# untitled.net
KiCad netlist of a schematic drawn in EAGLE
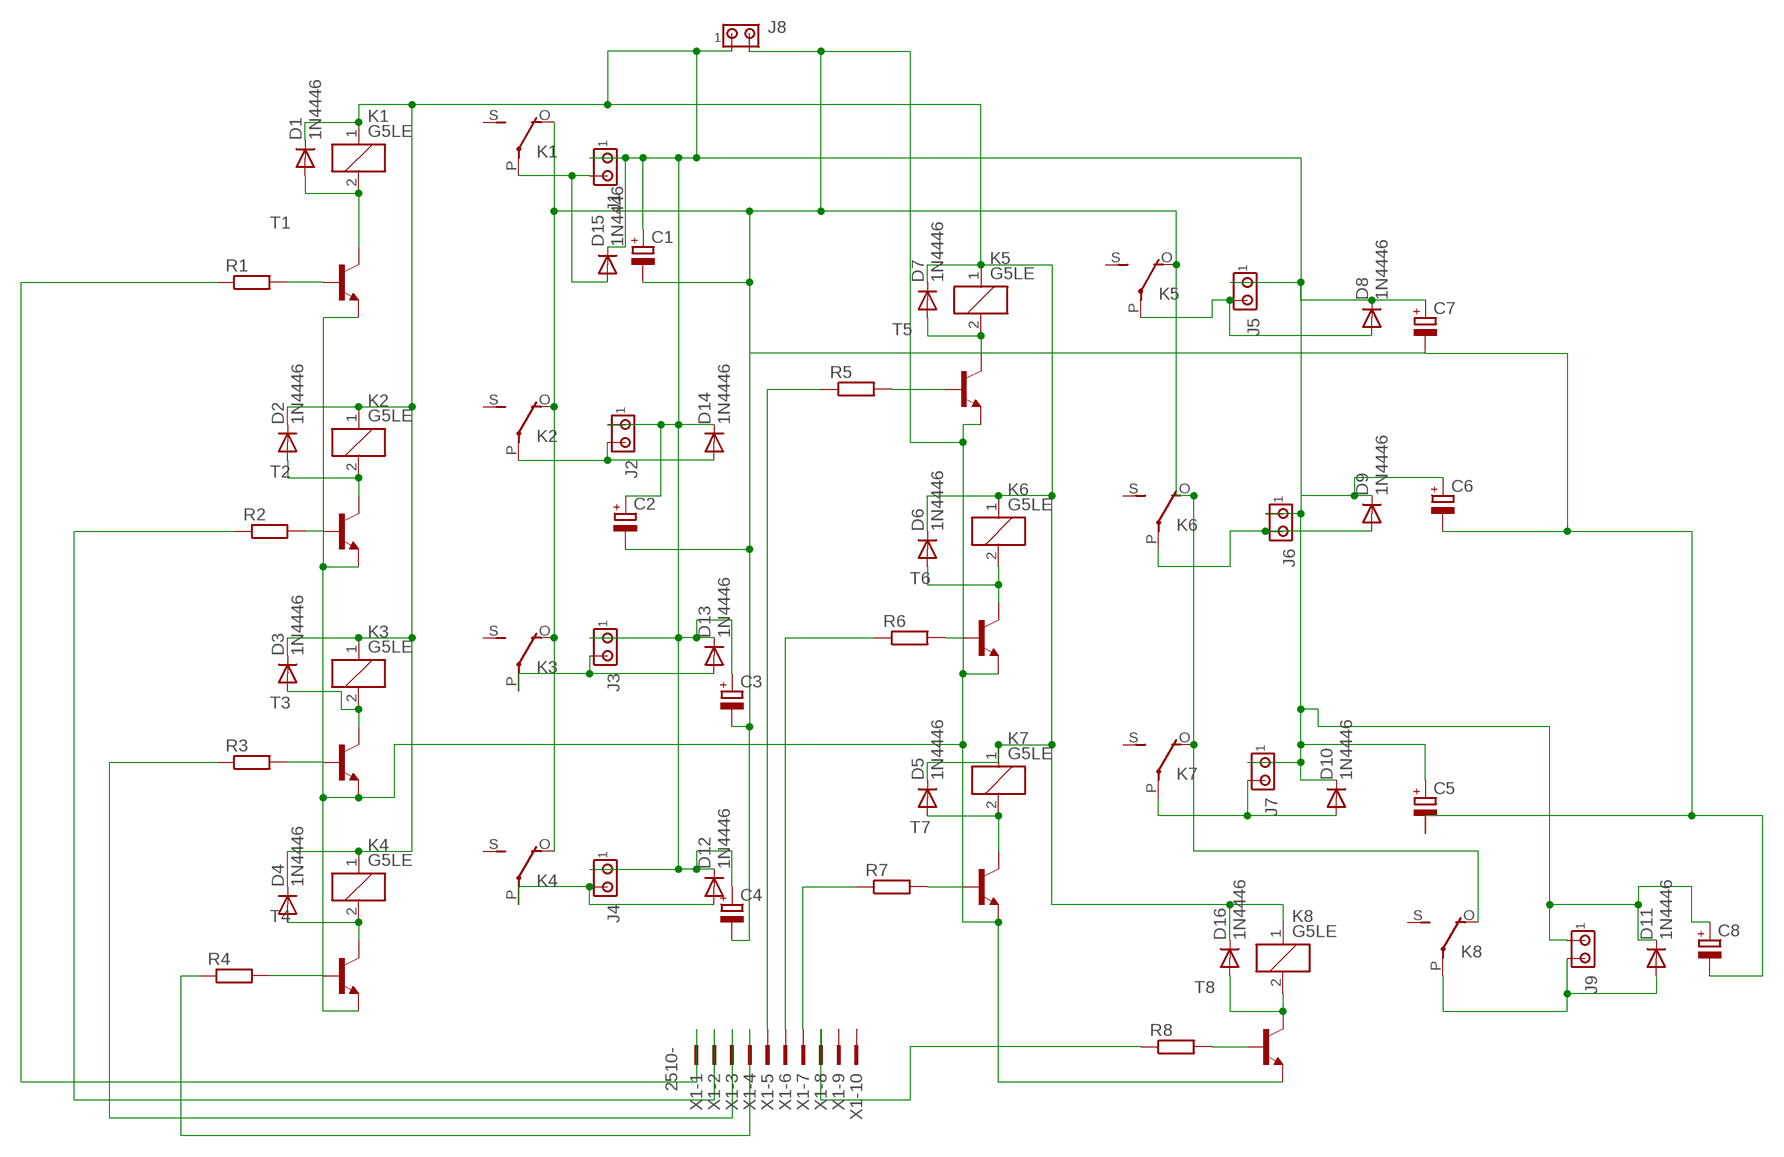
[diagram p0: schematic, sheet 1]

(export (version "E")
  (design (tool "Eeschema 10.0.6"))
  (components
    (comp (ref "C1")
      (value "CPOL-EUE5-10.5")
      (footprint "eagle-import:E5-10,5")
      (libsource (lib "eagle-import") (part "CPOL-EUE5-10.5"))
    )
    (comp (ref "C2")
      (value "CPOL-EUE5-10.5")
      (footprint "eagle-import:E5-10,5")
      (libsource (lib "eagle-import") (part "CPOL-EUE5-10.5"))
    )
    (comp (ref "C3")
      (value "CPOL-EUE5-10.5")
      (footprint "eagle-import:E5-10,5")
      (libsource (lib "eagle-import") (part "CPOL-EUE5-10.5"))
    )
    (comp (ref "C4")
      (value "CPOL-EUE5-10.5")
      (footprint "eagle-import:E5-10,5")
      (libsource (lib "eagle-import") (part "CPOL-EUE5-10.5"))
    )
    (comp (ref "C5")
      (value "CPOL-EUE5-10.5")
      (footprint "eagle-import:E5-10,5")
      (libsource (lib "eagle-import") (part "CPOL-EUE5-10.5"))
    )
    (comp (ref "C6")
      (value "CPOL-EUE5-10.5")
      (footprint "eagle-import:E5-10,5")
      (libsource (lib "eagle-import") (part "CPOL-EUE5-10.5"))
    )
    (comp (ref "C7")
      (value "CPOL-EUE5-10.5")
      (footprint "eagle-import:E5-10,5")
      (libsource (lib "eagle-import") (part "CPOL-EUE5-10.5"))
    )
    (comp (ref "C8")
      (value "CPOL-EUE5-10.5")
      (footprint "eagle-import:E5-10,5")
      (libsource (lib "eagle-import") (part "CPOL-EUE5-10.5"))
    )
    (comp (ref "D1")
      (value "1N4446")
      (footprint "eagle-import:DO35-10")
      (libsource (lib "eagle-import") (part "1N4446"))
    )
    (comp (ref "D2")
      (value "1N4446")
      (footprint "eagle-import:DO35-10")
      (libsource (lib "eagle-import") (part "1N4446"))
    )
    (comp (ref "D3")
      (value "1N4446")
      (footprint "eagle-import:DO35-10")
      (libsource (lib "eagle-import") (part "1N4446"))
    )
    (comp (ref "D4")
      (value "1N4446")
      (footprint "eagle-import:DO35-10")
      (libsource (lib "eagle-import") (part "1N4446"))
    )
    (comp (ref "D5")
      (value "1N4446")
      (footprint "eagle-import:DO35-10")
      (libsource (lib "eagle-import") (part "1N4446"))
    )
    (comp (ref "D6")
      (value "1N4446")
      (footprint "eagle-import:DO35-10")
      (libsource (lib "eagle-import") (part "1N4446"))
    )
    (comp (ref "D7")
      (value "1N4446")
      (footprint "eagle-import:DO35-10")
      (libsource (lib "eagle-import") (part "1N4446"))
    )
    (comp (ref "D8")
      (value "1N4446")
      (footprint "eagle-import:DO35-10")
      (libsource (lib "eagle-import") (part "1N4446"))
    )
    (comp (ref "D9")
      (value "1N4446")
      (footprint "eagle-import:DO35-10")
      (libsource (lib "eagle-import") (part "1N4446"))
    )
    (comp (ref "D10")
      (value "1N4446")
      (footprint "eagle-import:DO35-10")
      (libsource (lib "eagle-import") (part "1N4446"))
    )
    (comp (ref "D11")
      (value "1N4446")
      (footprint "eagle-import:DO35-10")
      (libsource (lib "eagle-import") (part "1N4446"))
    )
    (comp (ref "D12")
      (value "1N4446")
      (footprint "eagle-import:DO35-10")
      (libsource (lib "eagle-import") (part "1N4446"))
    )
    (comp (ref "D13")
      (value "1N4446")
      (footprint "eagle-import:DO35-10")
      (libsource (lib "eagle-import") (part "1N4446"))
    )
    (comp (ref "D14")
      (value "1N4446")
      (footprint "eagle-import:DO35-10")
      (libsource (lib "eagle-import") (part "1N4446"))
    )
    (comp (ref "D15")
      (value "1N4446")
      (footprint "eagle-import:DO35-10")
      (libsource (lib "eagle-import") (part "1N4446"))
    )
    (comp (ref "D16")
      (value "1N4446")
      (footprint "eagle-import:DO35-10")
      (libsource (lib "eagle-import") (part "1N4446"))
    )
    (comp (ref "J1")
      (value "MTA02-156")
      (footprint "eagle-import:1X2MTA")
      (libsource (lib "eagle-import") (part "MTA02-156"))
    )
    (comp (ref "J2")
      (value "MTA02-156")
      (footprint "eagle-import:1X2MTA")
      (libsource (lib "eagle-import") (part "MTA02-156"))
    )
    (comp (ref "J3")
      (value "MTA02-156")
      (footprint "eagle-import:1X2MTA")
      (libsource (lib "eagle-import") (part "MTA02-156"))
    )
    (comp (ref "J4")
      (value "MTA02-156")
      (footprint "eagle-import:1X2MTA")
      (libsource (lib "eagle-import") (part "MTA02-156"))
    )
    (comp (ref "J5")
      (value "MTA02-156")
      (footprint "eagle-import:1X2MTA")
      (libsource (lib "eagle-import") (part "MTA02-156"))
    )
    (comp (ref "J6")
      (value "MTA02-156")
      (footprint "eagle-import:1X2MTA")
      (libsource (lib "eagle-import") (part "MTA02-156"))
    )
    (comp (ref "J7")
      (value "MTA02-156")
      (footprint "eagle-import:1X2MTA")
      (libsource (lib "eagle-import") (part "MTA02-156"))
    )
    (comp (ref "J8")
      (value "MTA02-156")
      (footprint "eagle-import:1X2MTA")
      (libsource (lib "eagle-import") (part "MTA02-156"))
    )
    (comp (ref "J9")
      (value "MTA02-156")
      (footprint "eagle-import:1X2MTA")
      (libsource (lib "eagle-import") (part "MTA02-156"))
    )
    (comp (ref "K1")
      (value "G5LE")
      (footprint "eagle-import:G5LE")
      (libsource (lib "eagle-import") (part "G5LE"))
    )
    (comp (ref "K2")
      (value "G5LE")
      (footprint "eagle-import:G5LE")
      (libsource (lib "eagle-import") (part "G5LE"))
    )
    (comp (ref "K3")
      (value "G5LE")
      (footprint "eagle-import:G5LE")
      (libsource (lib "eagle-import") (part "G5LE"))
    )
    (comp (ref "K4")
      (value "G5LE")
      (footprint "eagle-import:G5LE")
      (libsource (lib "eagle-import") (part "G5LE"))
    )
    (comp (ref "K5")
      (value "G5LE")
      (footprint "eagle-import:G5LE")
      (libsource (lib "eagle-import") (part "G5LE"))
    )
    (comp (ref "K6")
      (value "G5LE")
      (footprint "eagle-import:G5LE")
      (libsource (lib "eagle-import") (part "G5LE"))
    )
    (comp (ref "K7")
      (value "G5LE")
      (footprint "eagle-import:G5LE")
      (libsource (lib "eagle-import") (part "G5LE"))
    )
    (comp (ref "K8")
      (value "G5LE")
      (footprint "eagle-import:G5LE")
      (fields (field (name "OC_FARNELL") "unknown") (field (name "OC_NEWARK") "unknown"))
      (libsource (lib "eagle-import") (part "G5LE"))
    )
    (comp (ref "R1")
      (value "R-EU_0207/10")
      (footprint "eagle-import:0207_10")
      (libsource (lib "eagle-import") (part "R-EU_0207/10"))
    )
    (comp (ref "R2")
      (value "R-EU_0207/10")
      (footprint "eagle-import:0207_10")
      (libsource (lib "eagle-import") (part "R-EU_0207/10"))
    )
    (comp (ref "R3")
      (value "R-EU_0207/10")
      (footprint "eagle-import:0207_10")
      (libsource (lib "eagle-import") (part "R-EU_0207/10"))
    )
    (comp (ref "R4")
      (value "R-EU_0207/10")
      (footprint "eagle-import:0207_10")
      (libsource (lib "eagle-import") (part "R-EU_0207/10"))
    )
    (comp (ref "R5")
      (value "R-EU_0207/10")
      (footprint "eagle-import:0207_10")
      (libsource (lib "eagle-import") (part "R-EU_0207/10"))
    )
    (comp (ref "R6")
      (value "R-EU_0207/10")
      (footprint "eagle-import:0207_10")
      (libsource (lib "eagle-import") (part "R-EU_0207/10"))
    )
    (comp (ref "R7")
      (value "R-EU_0207/10")
      (footprint "eagle-import:0207_10")
      (libsource (lib "eagle-import") (part "R-EU_0207/10"))
    )
    (comp (ref "R8")
      (value "R-EU_0207/10")
      (footprint "eagle-import:0207_10")
      (libsource (lib "eagle-import") (part "R-EU_0207/10"))
    )
    (comp (ref "T1")
      (value "2N5401-NPN-TO92-CBE")
      (footprint "eagle-import:TO92-CBE")
      (libsource (lib "eagle-import") (part "-NPN-TO92-CBE2N5401"))
    )
    (comp (ref "T2")
      (value "2N5401-NPN-TO92-CBE")
      (footprint "eagle-import:TO92-CBE")
      (libsource (lib "eagle-import") (part "-NPN-TO92-CBE2N5401"))
    )
    (comp (ref "T3")
      (value "2N5401-NPN-TO92-CBE")
      (footprint "eagle-import:TO92-CBE")
      (libsource (lib "eagle-import") (part "-NPN-TO92-CBE2N5401"))
    )
    (comp (ref "T4")
      (value "2N5401-NPN-TO92-CBE")
      (footprint "eagle-import:TO92-CBE")
      (libsource (lib "eagle-import") (part "-NPN-TO92-CBE2N5401"))
    )
    (comp (ref "T5")
      (value "2N5401-NPN-TO92-CBE")
      (footprint "eagle-import:TO92-CBE")
      (libsource (lib "eagle-import") (part "-NPN-TO92-CBE2N5401"))
    )
    (comp (ref "T6")
      (value "2N5401-NPN-TO92-CBE")
      (footprint "eagle-import:TO92-CBE")
      (libsource (lib "eagle-import") (part "-NPN-TO92-CBE2N5401"))
    )
    (comp (ref "T7")
      (value "2N5401-NPN-TO92-CBE")
      (footprint "eagle-import:TO92-CBE")
      (libsource (lib "eagle-import") (part "-NPN-TO92-CBE2N5401"))
    )
    (comp (ref "T8")
      (value "2N5401-NPN-TO92-CBE")
      (footprint "eagle-import:TO92-CBE")
      (libsource (lib "eagle-import") (part "-NPN-TO92-CBE2N5401"))
    )
    (comp (ref "X1")
      (value "2510-")
      (footprint "eagle-import:PAK100_2500-10")
      (fields (field (name "MF") "3M") (field (name "MPN") "2510-6002UB"))
      (libsource (lib "eagle-import") (part "2510-"))
    )
  )
  (nets
    (net (code "1") (name "Net-(C1-Pad+)") (class "Default")
      (node (ref "C1") (pin "+") (pinfunction "+_+") (pintype "passive"))
      (node (ref "C2") (pin "+") (pinfunction "+_+") (pintype "passive"))
      (node (ref "C3") (pin "+") (pinfunction "+_+") (pintype "passive"))
      (node (ref "C4") (pin "+") (pinfunction "+_+") (pintype "passive"))
      (node (ref "C5") (pin "+") (pinfunction "+_+") (pintype "passive"))
      (node (ref "C6") (pin "+") (pinfunction "+_+") (pintype "passive"))
      (node (ref "C7") (pin "+") (pinfunction "+_+") (pintype "passive"))
      (node (ref "C8") (pin "+") (pinfunction "+_+") (pintype "passive"))
      (node (ref "D1") (pin "C") (pinfunction "C_C") (pintype "passive"))
      (node (ref "D10") (pin "C") (pinfunction "C_C") (pintype "passive"))
      (node (ref "D11") (pin "C") (pinfunction "C_C") (pintype "passive"))
      (node (ref "D12") (pin "C") (pinfunction "C_C") (pintype "passive"))
      (node (ref "D13") (pin "C") (pinfunction "C_C") (pintype "passive"))
      (node (ref "D14") (pin "C") (pinfunction "C_C") (pintype "passive"))
      (node (ref "D15") (pin "C") (pinfunction "C_C") (pintype "passive"))
      (node (ref "D16") (pin "C") (pinfunction "C_C") (pintype "passive"))
      (node (ref "D2") (pin "C") (pinfunction "C_C") (pintype "passive"))
      (node (ref "D3") (pin "C") (pinfunction "C_C") (pintype "passive"))
      (node (ref "D4") (pin "C") (pinfunction "C_C") (pintype "passive"))
      (node (ref "D5") (pin "C") (pinfunction "C_C") (pintype "passive"))
      (node (ref "D6") (pin "C") (pinfunction "C_C") (pintype "passive"))
      (node (ref "D7") (pin "C") (pinfunction "C_C") (pintype "passive"))
      (node (ref "D8") (pin "C") (pinfunction "C_C") (pintype "passive"))
      (node (ref "D9") (pin "C") (pinfunction "C_C") (pintype "passive"))
      (node (ref "J1") (pin "1") (pinfunction "1_1") (pintype "passive"))
      (node (ref "J2") (pin "1") (pinfunction "1_1") (pintype "passive"))
      (node (ref "J3") (pin "1") (pinfunction "1_1") (pintype "passive"))
      (node (ref "J4") (pin "1") (pinfunction "1_1") (pintype "passive"))
      (node (ref "J5") (pin "1") (pinfunction "1_1") (pintype "passive"))
      (node (ref "J6") (pin "1") (pinfunction "1_1") (pintype "passive"))
      (node (ref "J7") (pin "1") (pinfunction "1_1") (pintype "passive"))
      (node (ref "J8") (pin "1") (pinfunction "1_1") (pintype "passive"))
      (node (ref "J9") (pin "1") (pinfunction "1_1") (pintype "passive"))
      (node (ref "K1") (pin "1") (pinfunction "1_1") (pintype "passive"))
      (node (ref "K2") (pin "1") (pinfunction "1_1") (pintype "passive"))
      (node (ref "K3") (pin "1") (pinfunction "1_1") (pintype "passive"))
      (node (ref "K4") (pin "1") (pinfunction "1_1") (pintype "passive"))
      (node (ref "K5") (pin "1") (pinfunction "1_1") (pintype "passive"))
      (node (ref "K6") (pin "1") (pinfunction "1_1") (pintype "passive"))
      (node (ref "K7") (pin "1") (pinfunction "1_1") (pintype "passive"))
      (node (ref "K8") (pin "1") (pinfunction "1_1") (pintype "passive"))
    )
    (net (code "2") (name "Net-(C1-Pad-)") (class "Default")
      (node (ref "C1") (pin "-") (pinfunction "-_-") (pintype "passive"))
      (node (ref "C2") (pin "-") (pinfunction "-_-") (pintype "passive"))
      (node (ref "C3") (pin "-") (pinfunction "-_-") (pintype "passive"))
      (node (ref "C4") (pin "-") (pinfunction "-_-") (pintype "passive"))
      (node (ref "C5") (pin "-") (pinfunction "-_-") (pintype "passive"))
      (node (ref "C6") (pin "-") (pinfunction "-_-") (pintype "passive"))
      (node (ref "C7") (pin "-") (pinfunction "-_-") (pintype "passive"))
      (node (ref "C8") (pin "-") (pinfunction "-_-") (pintype "passive"))
      (node (ref "J8") (pin "2") (pinfunction "2_2") (pintype "passive"))
      (node (ref "K1") (pin "O") (pinfunction "O_O") (pintype "passive"))
      (node (ref "K2") (pin "O") (pinfunction "O_O") (pintype "passive"))
      (node (ref "K3") (pin "O") (pinfunction "O_O") (pintype "passive"))
      (node (ref "K4") (pin "O") (pinfunction "O_O") (pintype "passive"))
      (node (ref "K5") (pin "O") (pinfunction "O_O") (pintype "passive"))
      (node (ref "K6") (pin "O") (pinfunction "O_O") (pintype "passive"))
      (node (ref "K7") (pin "O") (pinfunction "O_O") (pintype "passive"))
      (node (ref "K8") (pin "O") (pinfunction "O_O") (pintype "passive"))
      (node (ref "T1") (pin "E") (pinfunction "E_E") (pintype "passive"))
      (node (ref "T2") (pin "E") (pinfunction "E_E") (pintype "passive"))
      (node (ref "T3") (pin "E") (pinfunction "E_E") (pintype "passive"))
      (node (ref "T4") (pin "E") (pinfunction "E_E") (pintype "passive"))
      (node (ref "T5") (pin "E") (pinfunction "E_E") (pintype "passive"))
      (node (ref "T6") (pin "E") (pinfunction "E_E") (pintype "passive"))
      (node (ref "T7") (pin "E") (pinfunction "E_E") (pintype "passive"))
      (node (ref "T8") (pin "E") (pinfunction "E_E") (pintype "passive"))
    )
    (net (code "3") (name "Net-(D1-PadA)") (class "Default")
      (node (ref "D1") (pin "A") (pinfunction "A_A") (pintype "passive"))
      (node (ref "K1") (pin "2") (pinfunction "2_2") (pintype "passive"))
      (node (ref "T1") (pin "C") (pinfunction "C_C") (pintype "passive"))
    )
    (net (code "4") (name "Net-(D2-PadA)") (class "Default")
      (node (ref "D2") (pin "A") (pinfunction "A_A") (pintype "passive"))
      (node (ref "K2") (pin "2") (pinfunction "2_2") (pintype "passive"))
      (node (ref "T2") (pin "C") (pinfunction "C_C") (pintype "passive"))
    )
    (net (code "5") (name "Net-(D3-PadA)") (class "Default")
      (node (ref "D3") (pin "A") (pinfunction "A_A") (pintype "passive"))
      (node (ref "K3") (pin "2") (pinfunction "2_2") (pintype "passive"))
      (node (ref "T3") (pin "C") (pinfunction "C_C") (pintype "passive"))
    )
    (net (code "6") (name "Net-(D4-PadA)") (class "Default")
      (node (ref "D4") (pin "A") (pinfunction "A_A") (pintype "passive"))
      (node (ref "K4") (pin "2") (pinfunction "2_2") (pintype "passive"))
      (node (ref "T4") (pin "C") (pinfunction "C_C") (pintype "passive"))
    )
    (net (code "7") (name "Net-(D5-PadA)") (class "Default")
      (node (ref "D5") (pin "A") (pinfunction "A_A") (pintype "passive"))
      (node (ref "K7") (pin "2") (pinfunction "2_2") (pintype "passive"))
      (node (ref "T7") (pin "C") (pinfunction "C_C") (pintype "passive"))
    )
    (net (code "8") (name "Net-(D6-PadA)") (class "Default")
      (node (ref "D6") (pin "A") (pinfunction "A_A") (pintype "passive"))
      (node (ref "K6") (pin "2") (pinfunction "2_2") (pintype "passive"))
      (node (ref "T6") (pin "C") (pinfunction "C_C") (pintype "passive"))
    )
    (net (code "9") (name "Net-(D7-PadA)") (class "Default")
      (node (ref "D7") (pin "A") (pinfunction "A_A") (pintype "passive"))
      (node (ref "K5") (pin "2") (pinfunction "2_2") (pintype "passive"))
      (node (ref "T5") (pin "C") (pinfunction "C_C") (pintype "passive"))
    )
    (net (code "10") (name "Net-(D8-PadA)") (class "Default")
      (node (ref "D8") (pin "A") (pinfunction "A_A") (pintype "passive"))
      (node (ref "J5") (pin "2") (pinfunction "2_2") (pintype "passive"))
      (node (ref "K5") (pin "P") (pinfunction "P_P") (pintype "passive"))
    )
    (net (code "11") (name "Net-(D9-PadA)") (class "Default")
      (node (ref "D9") (pin "A") (pinfunction "A_A") (pintype "passive"))
      (node (ref "J6") (pin "2") (pinfunction "2_2") (pintype "passive"))
      (node (ref "K6") (pin "P") (pinfunction "P_P") (pintype "passive"))
    )
    (net (code "12") (name "Net-(D10-PadA)") (class "Default")
      (node (ref "D10") (pin "A") (pinfunction "A_A") (pintype "passive"))
      (node (ref "J7") (pin "2") (pinfunction "2_2") (pintype "passive"))
      (node (ref "K7") (pin "P") (pinfunction "P_P") (pintype "passive"))
    )
    (net (code "13") (name "Net-(D11-PadA)") (class "Default")
      (node (ref "D11") (pin "A") (pinfunction "A_A") (pintype "passive"))
      (node (ref "J9") (pin "2") (pinfunction "2_2") (pintype "passive"))
      (node (ref "K8") (pin "P") (pinfunction "P_P") (pintype "passive"))
    )
    (net (code "14") (name "Net-(D12-PadA)") (class "Default")
      (node (ref "D12") (pin "A") (pinfunction "A_A") (pintype "passive"))
      (node (ref "J4") (pin "2") (pinfunction "2_2") (pintype "passive"))
      (node (ref "K4") (pin "P") (pinfunction "P_P") (pintype "passive"))
    )
    (net (code "15") (name "Net-(D13-PadA)") (class "Default")
      (node (ref "D13") (pin "A") (pinfunction "A_A") (pintype "passive"))
      (node (ref "J3") (pin "2") (pinfunction "2_2") (pintype "passive"))
      (node (ref "K3") (pin "P") (pinfunction "P_P") (pintype "passive"))
    )
    (net (code "16") (name "Net-(D14-PadA)") (class "Default")
      (node (ref "D14") (pin "A") (pinfunction "A_A") (pintype "passive"))
      (node (ref "J2") (pin "2") (pinfunction "2_2") (pintype "passive"))
      (node (ref "K2") (pin "P") (pinfunction "P_P") (pintype "passive"))
    )
    (net (code "17") (name "Net-(D15-PadA)") (class "Default")
      (node (ref "D15") (pin "A") (pinfunction "A_A") (pintype "passive"))
      (node (ref "J1") (pin "2") (pinfunction "2_2") (pintype "passive"))
      (node (ref "K1") (pin "P") (pinfunction "P_P") (pintype "passive"))
    )
    (net (code "18") (name "Net-(D16-PadA)") (class "Default")
      (node (ref "D16") (pin "A") (pinfunction "A_A") (pintype "passive"))
      (node (ref "K8") (pin "2") (pinfunction "2_2") (pintype "passive"))
      (node (ref "T8") (pin "C") (pinfunction "C_C") (pintype "passive"))
    )
    (net (code "19") (name "Net-(R1-Pad2)") (class "Default")
      (node (ref "R1") (pin "2") (pinfunction "2_2") (pintype "passive"))
      (node (ref "T1") (pin "B") (pinfunction "B_B") (pintype "passive"))
    )
    (net (code "20") (name "Net-(R2-Pad2)") (class "Default")
      (node (ref "R2") (pin "2") (pinfunction "2_2") (pintype "passive"))
      (node (ref "T2") (pin "B") (pinfunction "B_B") (pintype "passive"))
    )
    (net (code "21") (name "Net-(R3-Pad2)") (class "Default")
      (node (ref "R3") (pin "2") (pinfunction "2_2") (pintype "passive"))
      (node (ref "T3") (pin "B") (pinfunction "B_B") (pintype "passive"))
    )
    (net (code "22") (name "Net-(R4-Pad2)") (class "Default")
      (node (ref "R4") (pin "2") (pinfunction "2_2") (pintype "passive"))
      (node (ref "T4") (pin "B") (pinfunction "B_B") (pintype "passive"))
    )
    (net (code "23") (name "Net-(R5-Pad2)") (class "Default")
      (node (ref "R5") (pin "2") (pinfunction "2_2") (pintype "passive"))
      (node (ref "T5") (pin "B") (pinfunction "B_B") (pintype "passive"))
    )
    (net (code "24") (name "Net-(R6-Pad2)") (class "Default")
      (node (ref "R6") (pin "2") (pinfunction "2_2") (pintype "passive"))
      (node (ref "T6") (pin "B") (pinfunction "B_B") (pintype "passive"))
    )
    (net (code "25") (name "Net-(R7-Pad2)") (class "Default")
      (node (ref "R7") (pin "2") (pinfunction "2_2") (pintype "passive"))
      (node (ref "T7") (pin "B") (pinfunction "B_B") (pintype "passive"))
    )
    (net (code "26") (name "Net-(R8-Pad2)") (class "Default")
      (node (ref "R8") (pin "2") (pinfunction "2_2") (pintype "passive"))
      (node (ref "T8") (pin "B") (pinfunction "B_B") (pintype "passive"))
    )
    (net (code "27") (name "Net-(X1A-KL)") (class "Default")
      (node (ref "R1") (pin "1") (pinfunction "1_1") (pintype "passive"))
      (node (ref "X1") (pin "1") (pinfunction "KL_1") (pintype "passive"))
    )
    (net (code "28") (name "Net-(X1C-KL)") (class "Default")
      (node (ref "R2") (pin "1") (pinfunction "1_1") (pintype "passive"))
      (node (ref "X1") (pin "2") (pinfunction "KL_2") (pintype "passive"))
    )
    (net (code "29") (name "Net-(X1D-KL)") (class "Default")
      (node (ref "R3") (pin "1") (pinfunction "1_1") (pintype "passive"))
      (node (ref "X1") (pin "3") (pinfunction "KL_3") (pintype "passive"))
    )
    (net (code "30") (name "Net-(X1E-KL)") (class "Default")
      (node (ref "R4") (pin "1") (pinfunction "1_1") (pintype "passive"))
      (node (ref "X1") (pin "4") (pinfunction "KL_4") (pintype "passive"))
    )
    (net (code "31") (name "Net-(X1F-KL)") (class "Default")
      (node (ref "R5") (pin "1") (pinfunction "1_1") (pintype "passive"))
      (node (ref "X1") (pin "5") (pinfunction "KL_5") (pintype "passive"))
    )
    (net (code "32") (name "Net-(X1G-KL)") (class "Default")
      (node (ref "R6") (pin "1") (pinfunction "1_1") (pintype "passive"))
      (node (ref "X1") (pin "6") (pinfunction "KL_6") (pintype "passive"))
    )
    (net (code "33") (name "Net-(X1H-KL)") (class "Default")
      (node (ref "R7") (pin "1") (pinfunction "1_1") (pintype "passive"))
      (node (ref "X1") (pin "7") (pinfunction "KL_7") (pintype "passive"))
    )
    (net (code "34") (name "Net-(X1I-KL)") (class "Default")
      (node (ref "R8") (pin "1") (pinfunction "1_1") (pintype "passive"))
      (node (ref "X1") (pin "8") (pinfunction "KL_8") (pintype "passive"))
    )
    (net (code "35") (name "unconnected-(K1-PadS)") (class "Default")
      (node (ref "K1") (pin "S") (pinfunction "S_S") (pintype "passive"))
    )
    (net (code "36") (name "unconnected-(K2-PadS)") (class "Default")
      (node (ref "K2") (pin "S") (pinfunction "S_S") (pintype "passive"))
    )
    (net (code "37") (name "unconnected-(K3-PadS)") (class "Default")
      (node (ref "K3") (pin "S") (pinfunction "S_S") (pintype "passive"))
    )
    (net (code "38") (name "unconnected-(K4-PadS)") (class "Default")
      (node (ref "K4") (pin "S") (pinfunction "S_S") (pintype "passive"))
    )
    (net (code "39") (name "unconnected-(K5-PadS)") (class "Default")
      (node (ref "K5") (pin "S") (pinfunction "S_S") (pintype "passive"))
    )
    (net (code "40") (name "unconnected-(K6-PadS)") (class "Default")
      (node (ref "K6") (pin "S") (pinfunction "S_S") (pintype "passive"))
    )
    (net (code "41") (name "unconnected-(K7-PadS)") (class "Default")
      (node (ref "K7") (pin "S") (pinfunction "S_S") (pintype "passive"))
    )
    (net (code "42") (name "unconnected-(K8-PadS)") (class "Default")
      (node (ref "K8") (pin "S") (pinfunction "S_S") (pintype "passive"))
    )
    (net (code "43") (name "unconnected-(X1B-KL-Pad10)") (class "Default")
      (node (ref "X1") (pin "10") (pinfunction "KL_10") (pintype "passive"))
    )
    (net (code "44") (name "unconnected-(X1J-KL-Pad9)") (class "Default")
      (node (ref "X1") (pin "9") (pinfunction "KL_9") (pintype "passive"))
    )
  )
)
